# Power_Board.net
KiCad netlist of a schematic drawn in EAGLE
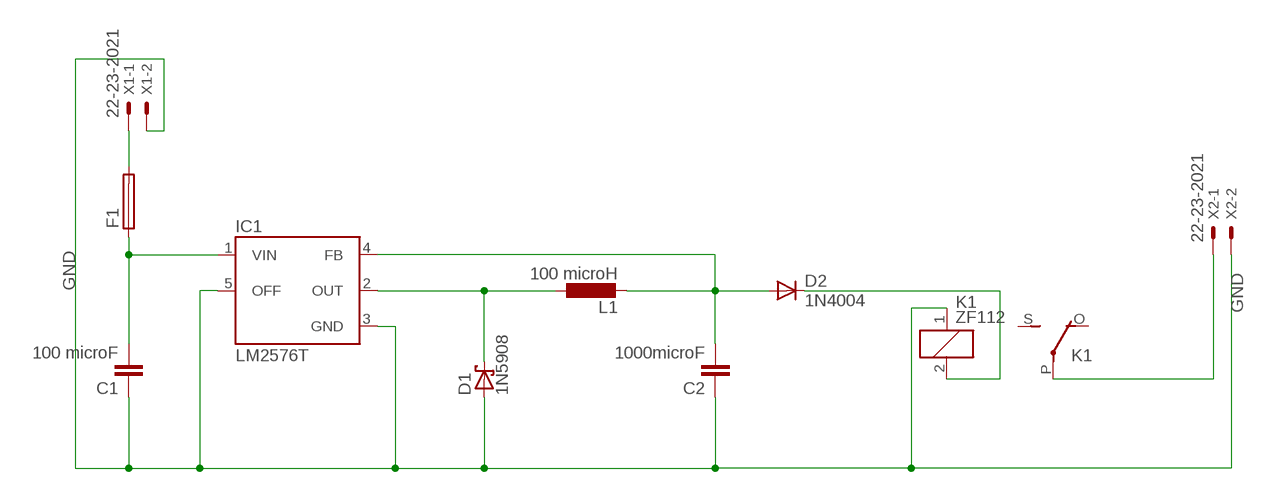
[diagram p0: schematic, sheet 1]

(export (version "E")
  (design (tool "Eeschema 10.0.6"))
  (components
    (comp (ref "C1")
      (value "100 microF")
      (footprint "eagle-import:C050-030X075")
      (libsource (lib "eagle-import") (part "C-EU050-030X075"))
    )
    (comp (ref "C2")
      (value "1000microF")
      (footprint "eagle-import:C050-030X075")
      (libsource (lib "eagle-import") (part "C-EU050-030X075"))
    )
    (comp (ref "D1")
      (value "1N5908")
      (footprint "eagle-import:C4111-15")
      (libsource (lib "eagle-import") (part "1N5908"))
    )
    (comp (ref "D2")
      (value "1N4004")
      (footprint "eagle-import:DO41-10")
      (libsource (lib "eagle-import") (part "1N4004"))
    )
    (comp (ref "F1")
      (value "FUSESH22,5")
      (footprint "eagle-import:SH22,5")
      (libsource (lib "eagle-import") (part "FUSESH22,5"))
    )
    (comp (ref "IC1")
      (value "LM2576T")
      (footprint "eagle-import:TO220-5")
      (libsource (lib "eagle-import") (part "LM2576T"))
    )
    (comp (ref "K1")
      (value "ZF112")
      (footprint "eagle-import:ZF112")
      (libsource (lib "eagle-import") (part "ZF112"))
    )
    (comp (ref "L1")
      (value "100 microH")
      (footprint "eagle-import:0204_7")
      (libsource (lib "eagle-import") (part "L-EU0204/7"))
    )
    (comp (ref "X1")
      (value "22-23-2021")
      (footprint "eagle-import:22-23-2021")
      (fields (field (name "MF") "MOLEX"))
      (libsource (lib "eagle-import") (part "22-23-2021"))
    )
    (comp (ref "X2")
      (value "22-23-2021")
      (footprint "eagle-import:22-23-2021")
      (fields (field (name "MF") "MOLEX"))
      (libsource (lib "eagle-import") (part "22-23-2021"))
    )
  )
  (nets
    (net (code "1") (name "/GND") (class "Default")
      (node (ref "C1") (pin "1") (pinfunction "1_1") (pintype "passive"))
      (node (ref "C2") (pin "1") (pinfunction "1_1") (pintype "passive"))
      (node (ref "D1") (pin "A") (pinfunction "A_A") (pintype "passive"))
      (node (ref "IC1") (pin "3") (pinfunction "GND_3") (pintype "power_in"))
      (node (ref "IC1") (pin "5") (pinfunction "OFF_5") (pintype "input"))
      (node (ref "K1") (pin "1") (pinfunction "1_1") (pintype "passive"))
      (node (ref "X1") (pin "2") (pinfunction "S_2") (pintype "passive"))
      (node (ref "X2") (pin "2") (pinfunction "S_2") (pintype "passive"))
    )
    (net (code "2") (name "Net-(D2-PadC)") (class "Default")
      (node (ref "D2") (pin "C") (pinfunction "C_C") (pintype "passive"))
      (node (ref "K1") (pin "2") (pinfunction "2_2") (pintype "passive"))
    )
    (net (code "3") (name "Net-(IC1-FB)") (class "Default")
      (node (ref "C2") (pin "2") (pinfunction "2_2") (pintype "passive"))
      (node (ref "D2") (pin "A") (pinfunction "A_A") (pintype "passive"))
      (node (ref "IC1") (pin "4") (pinfunction "FB_4") (pintype "input"))
      (node (ref "L1") (pin "2") (pinfunction "2_2") (pintype "passive"))
    )
    (net (code "4") (name "Net-(IC1-OUT)") (class "Default")
      (node (ref "D1") (pin "C") (pinfunction "C_C") (pintype "passive"))
      (node (ref "IC1") (pin "2") (pinfunction "OUT_2") (pintype "output"))
      (node (ref "L1") (pin "1") (pinfunction "1_1") (pintype "passive"))
    )
    (net (code "5") (name "Net-(IC1-VIN)") (class "Default")
      (node (ref "C1") (pin "2") (pinfunction "2_2") (pintype "passive"))
      (node (ref "F1") (pin "1") (pinfunction "1_1") (pintype "passive"))
      (node (ref "IC1") (pin "1") (pinfunction "VIN_1") (pintype "power_in"))
    )
    (net (code "6") (name "Net-(X1A-S)") (class "Default")
      (node (ref "F1") (pin "2") (pinfunction "2_2") (pintype "passive"))
      (node (ref "X1") (pin "1") (pinfunction "S_1") (pintype "passive"))
    )
    (net (code "7") (name "Net-(X2A-S)") (class "Default")
      (node (ref "K1") (pin "P") (pinfunction "P_P") (pintype "passive"))
      (node (ref "X2") (pin "1") (pinfunction "S_1") (pintype "passive"))
    )
    (net (code "8") (name "unconnected-(K1-PadO)") (class "Default")
      (node (ref "K1") (pin "O") (pinfunction "O_O") (pintype "passive"))
    )
    (net (code "9") (name "unconnected-(K1-PadS)") (class "Default")
      (node (ref "K1") (pin "S") (pinfunction "S_S") (pintype "passive"))
    )
  )
)
